# TPS54202.net
KiCad netlist of a schematic drawn in Altium Designer
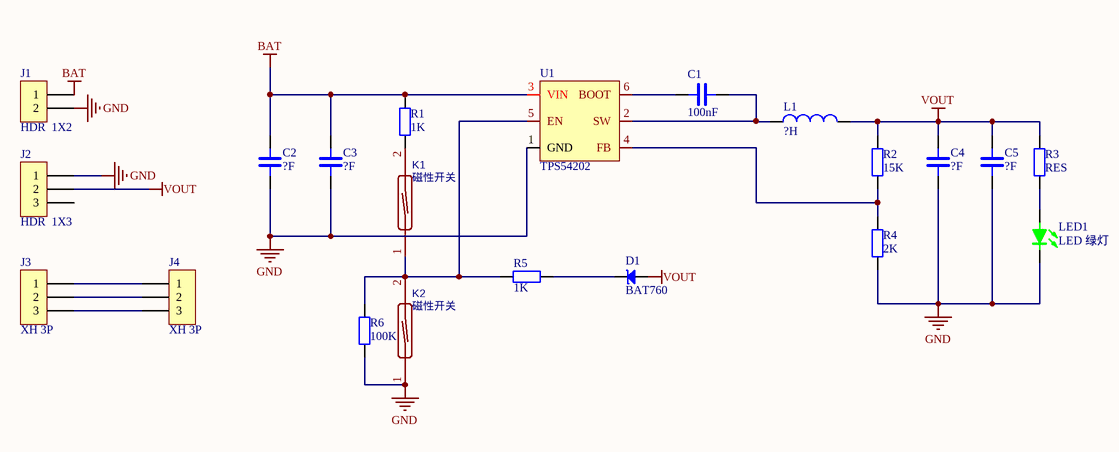
[diagram p0: 飞镖电源TPS54202.SchDoc]

(export (version "E")
  (design (tool "Eeschema 10.0.6"))
  (components
    (comp (ref "C1")
      (value "100nF")
      (footprint "C 0603")
      (description "Capacitor")
      (libsource (lib "General") (part "CAP"))
    )
    (comp (ref "C2")
      (value "?F")
      (footprint "C 1206")
      (description "Capacitor")
      (libsource (lib "General") (part "CAP"))
    )
    (comp (ref "C3")
      (value "?F")
      (footprint "C 1206")
      (description "Capacitor")
      (libsource (lib "General") (part "CAP"))
    )
    (comp (ref "C4")
      (value "?F")
      (footprint "C 1206")
      (description "Capacitor")
      (libsource (lib "General") (part "CAP"))
    )
    (comp (ref "C5")
      (value "?F")
      (footprint "C 1206")
      (description "Capacitor")
      (libsource (lib "General") (part "CAP"))
    )
    (comp (ref "D1")
      (value "BAT760")
      (footprint "SOD-323")
      (description "肖特基二极管")
      (libsource (lib "General") (part "BAT760"))
    )
    (comp (ref "J1")
      (value "HDR  1X2")
      (footprint "HDR2.54 D-L-F-1X2P")
      (description "Connector")
      (libsource (lib "General") (part "HDR  1X2"))
    )
    (comp (ref "J2")
      (value "HDR  1X3")
      (footprint "HDR2.54 D-L-F-1X3P")
      (description "Connector")
      (libsource (lib "General") (part "HDR  1X3"))
    )
    (comp (ref "J3")
      (value "XH 3P")
      (footprint "XH2.54-3P")
      (description "Connector")
      (libsource (lib "General") (part "XH 3P"))
    )
    (comp (ref "J4")
      (value "XH 3P")
      (footprint "XH2.54-3P")
      (description "Connector")
      (libsource (lib "") (part "XH 3P_1"))
    )
    (comp (ref "K1")
      (value "磁性开关")
      (footprint "*MKA14103")
      (description "开关")
      (fields
        (field (name "BOM_SUPPLIER PART") "C575284")
        (field (name "BOM_MANUFACTURER PART") "KSK-SME560-1015")
        (field (name "CONTRIBUTOR") "LCSC")
      )
      (libsource (lib "General") (part "干簧管"))
    )
    (comp (ref "K2")
      (value "磁性开关")
      (footprint "*MKA14103")
      (description "开关")
      (fields
        (field (name "BOM_SUPPLIER PART") "C575284")
        (field (name "BOM_MANUFACTURER PART") "KSK-SME560-1015")
        (field (name "CONTRIBUTOR") "LCSC")
      )
      (libsource (lib "General") (part "干簧管"))
    )
    (comp (ref "L1")
      (value "?H")
      (footprint "SMD 7*7*4")
      (description "Inductor")
      (fields (field (name "PUBLISHER") "Altium Limited"))
      (libsource (lib "General") (part "Inductor"))
    )
    (comp (ref "LED1")
      (value "LED 绿灯")
      (footprint "LED 0603-G")
      (description "LED")
      (libsource (lib "General") (part "LED 绿灯"))
    )
    (comp (ref "R1")
      (value "1K")
      (footprint "R 0603")
      (description "Resistor")
      (libsource (lib "General") (part "RES"))
    )
    (comp (ref "R2")
      (value "15K")
      (footprint "R 0603")
      (description "Resistor")
      (libsource (lib "General") (part "RES"))
    )
    (comp (ref "R3")
      (value "RES")
      (footprint "R 0603")
      (description "Resistor")
      (libsource (lib "General") (part "RES"))
    )
    (comp (ref "R4")
      (value "2K")
      (footprint "R 0603")
      (description "Resistor")
      (libsource (lib "General") (part "RES"))
    )
    (comp (ref "R5")
      (value "1K")
      (footprint "R 0603")
      (description "Resistor")
      (libsource (lib "") (part "RES_1"))
    )
    (comp (ref "R6")
      (value "100K")
      (footprint "R 0603")
      (description "Resistor")
      (libsource (lib "General") (part "RES"))
    )
    (comp (ref "U1")
      (value "TPS54202")
      (footprint "SOT23-6")
      (description "DC-DC 降压芯片")
      (fields
        (field (name "BOM_SUPPLIER PART") "C431540")
        (field (name "BOM_MANUFACTURER PART") "MSK12C02")
        (field (name "CONTRIBUTOR") "LCSC")
      )
      (libsource (lib "General") (part "TPS54202"))
    )
  )
  (nets
    (net (code "1") (name "BAT") (class "Default")
      (node (ref "C2") (pin "2") (pinfunction "2_2") (pintype "passive"))
      (node (ref "C3") (pin "2") (pinfunction "2_2") (pintype "passive"))
      (node (ref "J1") (pin "1") (pinfunction "1_1") (pintype "passive"))
      (node (ref "R1") (pin "2") (pinfunction "2_2") (pintype "passive"))
      (node (ref "U1") (pin "3") (pinfunction "VIN_3") (pintype "passive"))
    )
    (net (code "2") (name "GND") (class "Default")
      (node (ref "C2") (pin "1") (pinfunction "1_1") (pintype "passive"))
      (node (ref "C3") (pin "1") (pinfunction "1_1") (pintype "passive"))
      (node (ref "C4") (pin "1") (pinfunction "1_1") (pintype "passive"))
      (node (ref "C5") (pin "1") (pinfunction "1_1") (pintype "passive"))
      (node (ref "J1") (pin "2") (pinfunction "2_2") (pintype "passive"))
      (node (ref "J2") (pin "1") (pinfunction "1_1") (pintype "passive"))
      (node (ref "K2") (pin "1") (pinfunction "1_1") (pintype "passive"))
      (node (ref "LED1") (pin "2") (pinfunction "C_2") (pintype "passive"))
      (node (ref "R4") (pin "1") (pinfunction "1_1") (pintype "passive"))
      (node (ref "R6") (pin "1") (pinfunction "1_1") (pintype "passive"))
      (node (ref "U1") (pin "1") (pinfunction "GND_1") (pintype "passive"))
    )
    (net (code "3") (name "Net-(D1-K)") (class "Default")
      (node (ref "D1") (pin "2") (pinfunction "K_2") (pintype "passive"))
      (node (ref "R5") (pin "2") (pinfunction "2_2") (pintype "passive"))
    )
    (net (code "4") (name "Net-(J3-Pad1)") (class "Default")
      (node (ref "J3") (pin "1") (pinfunction "1_1") (pintype "passive"))
      (node (ref "J4") (pin "1") (pinfunction "1_1") (pintype "passive"))
    )
    (net (code "5") (name "Net-(J3-Pad2)") (class "Default")
      (node (ref "J3") (pin "2") (pinfunction "2_2") (pintype "passive"))
      (node (ref "J4") (pin "2") (pinfunction "2_2") (pintype "passive"))
    )
    (net (code "6") (name "Net-(J3-Pad3)") (class "Default")
      (node (ref "J3") (pin "3") (pinfunction "3_3") (pintype "passive"))
      (node (ref "J4") (pin "3") (pinfunction "3_3") (pintype "passive"))
    )
    (net (code "7") (name "Net-(K1-Pad2)") (class "Default")
      (node (ref "K1") (pin "2") (pinfunction "2_2") (pintype "passive"))
      (node (ref "R1") (pin "1") (pinfunction "1_1") (pintype "passive"))
    )
    (net (code "8") (name "Net-(LED1-A)") (class "Default")
      (node (ref "LED1") (pin "1") (pinfunction "A_1") (pintype "passive"))
      (node (ref "R3") (pin "1") (pinfunction "1_1") (pintype "passive"))
    )
    (net (code "9") (name "Net-(U1-BOOT)") (class "Default")
      (node (ref "C1") (pin "1") (pinfunction "1_1") (pintype "passive"))
      (node (ref "U1") (pin "6") (pinfunction "BOOT_6") (pintype "passive"))
    )
    (net (code "10") (name "Net-(U1-EN)") (class "Default")
      (node (ref "K1") (pin "1") (pinfunction "1_1") (pintype "passive"))
      (node (ref "K2") (pin "2") (pinfunction "2_2") (pintype "passive"))
      (node (ref "R5") (pin "1") (pinfunction "1_1") (pintype "passive"))
      (node (ref "R6") (pin "2") (pinfunction "2_2") (pintype "passive"))
      (node (ref "U1") (pin "5") (pinfunction "EN_5") (pintype "passive"))
    )
    (net (code "11") (name "Net-(U1-FB)") (class "Default")
      (node (ref "R2") (pin "1") (pinfunction "1_1") (pintype "passive"))
      (node (ref "R4") (pin "2") (pinfunction "2_2") (pintype "passive"))
      (node (ref "U1") (pin "4") (pinfunction "FB_4") (pintype "passive"))
    )
    (net (code "12") (name "Net-(U1-SW)") (class "Default")
      (node (ref "C1") (pin "2") (pinfunction "2_2") (pintype "passive"))
      (node (ref "L1") (pin "1") (pinfunction "1_1") (pintype "passive"))
      (node (ref "U1") (pin "2") (pinfunction "SW_2") (pintype "passive"))
    )
    (net (code "13") (name "VOUT") (class "Default")
      (node (ref "C4") (pin "2") (pinfunction "2_2") (pintype "passive"))
      (node (ref "C5") (pin "2") (pinfunction "2_2") (pintype "passive"))
      (node (ref "D1") (pin "1") (pinfunction "A_1") (pintype "passive"))
      (node (ref "J2") (pin "2") (pinfunction "2_2") (pintype "passive"))
      (node (ref "L1") (pin "2") (pinfunction "2_2") (pintype "passive"))
      (node (ref "R2") (pin "2") (pinfunction "2_2") (pintype "passive"))
      (node (ref "R3") (pin "2") (pinfunction "2_2") (pintype "passive"))
    )
    (net (code "14") (name "unconnected-(J2-Pad3)") (class "Default")
      (node (ref "J2") (pin "3") (pinfunction "3_3") (pintype "passive"))
    )
  )
)
